# v1_1.net
KiCad netlist of a schematic drawn in Altium Designer
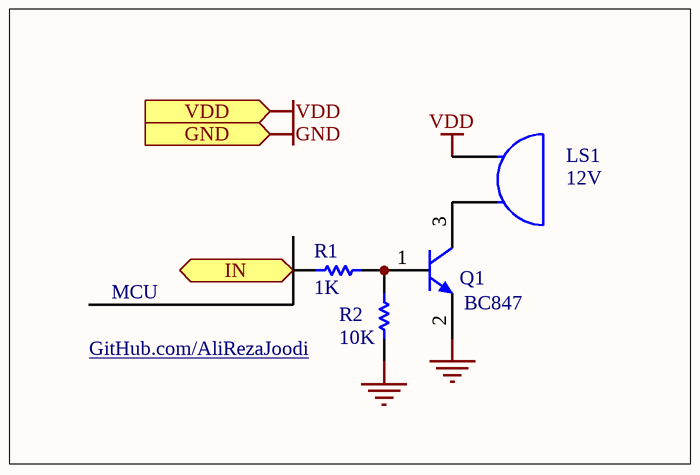
[diagram p0: v1.1.SchDoc]

(export (version "E")
  (design (tool "Eeschema 10.0.6"))
  (components
    (comp (ref "LS1")
      (value "12V")
      (footprint "RB_7.62mm")
      (description "Sounder")
      (fields
        (field (name "MANUFACTURER") "Generic Components")
        (field (name "Comment") "Buzzer")
        (field (name "PUBLISHER") "Altium Limited")
      )
      (libsource (lib "my Libraries") (part "Buzzer"))
    )
    (comp (ref "Q1")
      (value "BC847")
      (footprint "SOT23-3N")
      (description "Silicon Bipolar Transistor")
      (fields (field (name "Comment") "NPN"))
      (libsource (lib "my Libraries") (part "BC847"))
    )
    (comp (ref "R1")
      (value "1K")
      (footprint "0805")
      (description "Resistor")
      (fields (field (name "Comment") "Res1") (field (name "PUBLISHER") "Altium Limited"))
      (libsource (lib "Miscellaneous Devices") (part "Res1"))
    )
    (comp (ref "R2")
      (value "10K")
      (footprint "0805")
      (description "Resistor")
      (fields (field (name "Comment") "Res1") (field (name "PUBLISHER") "Altium Limited"))
      (libsource (lib "Miscellaneous Devices") (part "Res1"))
    )
  )
  (nets
    (net (code "1") (name "/IN") (class "Default")
      (node (ref "R1") (pin "2") (pinfunction "2_2") (pintype "passive"))
    )
    (net (code "2") (name "GND") (class "Default")
      (node (ref "Q1") (pin "2") (pinfunction "E_2") (pintype "passive"))
      (node (ref "R2") (pin "2") (pinfunction "2_2") (pintype "passive"))
    )
    (net (code "3") (name "Net-(LS1-B)") (class "Default")
      (node (ref "LS1") (pin "2") (pinfunction "B_2") (pintype "passive"))
      (node (ref "Q1") (pin "3") (pinfunction "C_3") (pintype "passive"))
    )
    (net (code "4") (name "Net-(Q1-B)") (class "Default")
      (node (ref "Q1") (pin "1") (pinfunction "B_1") (pintype "passive"))
      (node (ref "R1") (pin "1") (pinfunction "1_1") (pintype "passive"))
      (node (ref "R2") (pin "1") (pinfunction "1_1") (pintype "passive"))
    )
    (net (code "5") (name "VDD") (class "Default")
      (node (ref "LS1") (pin "1") (pinfunction "A_1") (pintype "passive"))
    )
  )
)
